# ndice.net
KiCad netlist of a schematic drawn in EAGLE
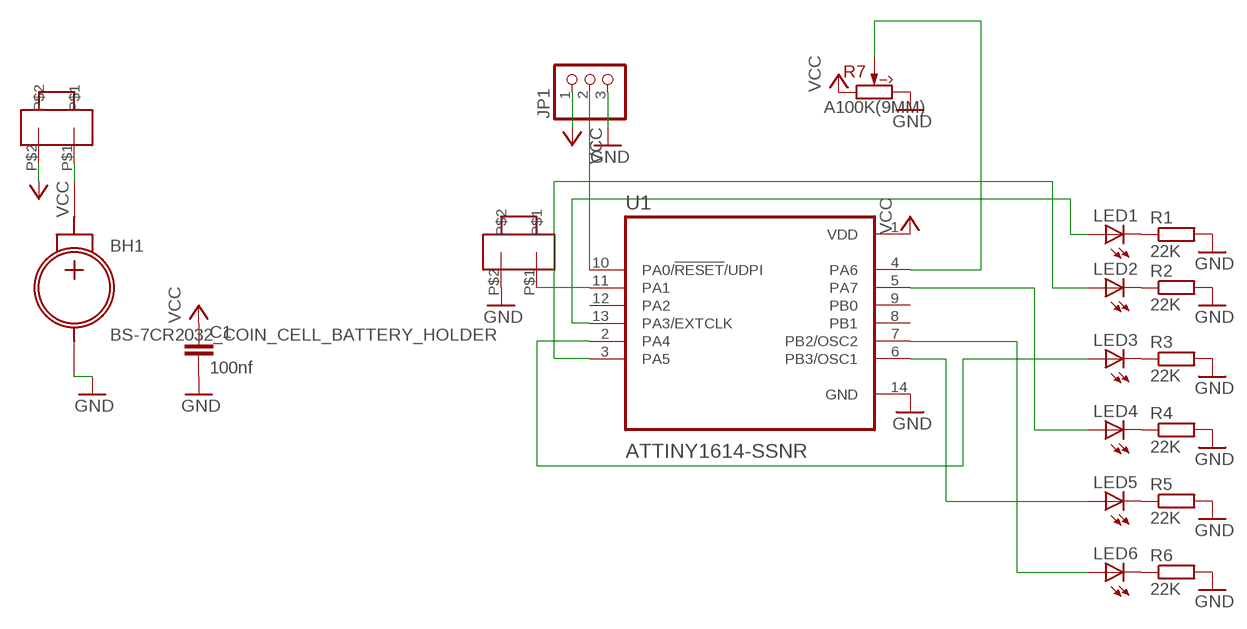
[diagram p0: schematic, sheet 1]

(export (version "E")
  (design (tool "Eeschema 10.0.6"))
  (components
    (comp (ref "BH1")
      (value "BS-7CR2032_COIN_CELL_BATTERY_HOLDER")
      (footprint "eagle-import:BS-7")
      (fields (field (name "MF") "MPD") (field (name "MP") "BS-7"))
      (libsource (lib "eagle-import") (part "BS-7CR2032_COIN_CELL_BATTERY_HOLDER"))
    )
    (comp (ref "C1")
      (value "100nf")
      (footprint "eagle-import:C0805")
      (libsource (lib "eagle-import") (part "C-EUC0805"))
    )
    (comp (ref "JP1")
      (value "PINHD-1X3CB")
      (footprint "eagle-import:1X03-CLEANBIG")
      (libsource (lib "eagle-import") (part "PINHD-1X3CB"))
    )
    (comp (ref "LED1")
      (value "LEDSML0805")
      (footprint "eagle-import:SML0805")
      (libsource (lib "eagle-import") (part "LEDSML0805"))
    )
    (comp (ref "LED2")
      (value "LEDSML0805")
      (footprint "eagle-import:SML0805")
      (libsource (lib "eagle-import") (part "LEDSML0805"))
    )
    (comp (ref "LED3")
      (value "LEDSML0805")
      (footprint "eagle-import:SML0805")
      (libsource (lib "eagle-import") (part "LEDSML0805"))
    )
    (comp (ref "LED4")
      (value "LEDSML0805")
      (footprint "eagle-import:SML0805")
      (libsource (lib "eagle-import") (part "LEDSML0805"))
    )
    (comp (ref "LED5")
      (value "LEDSML0805")
      (footprint "eagle-import:SML0805")
      (libsource (lib "eagle-import") (part "LEDSML0805"))
    )
    (comp (ref "LED6")
      (value "LEDSML0805")
      (footprint "eagle-import:SML0805")
      (libsource (lib "eagle-import") (part "LEDSML0805"))
    )
    (comp (ref "R1")
      (value "22K")
      (footprint "eagle-import:R0805")
      (libsource (lib "eagle-import") (part "R-EU_R0805"))
    )
    (comp (ref "R2")
      (value "22K")
      (footprint "eagle-import:R0805")
      (libsource (lib "eagle-import") (part "R-EU_R0805"))
    )
    (comp (ref "R3")
      (value "22K")
      (footprint "eagle-import:R0805")
      (libsource (lib "eagle-import") (part "R-EU_R0805"))
    )
    (comp (ref "R4")
      (value "22K")
      (footprint "eagle-import:R0805")
      (libsource (lib "eagle-import") (part "R-EU_R0805"))
    )
    (comp (ref "R5")
      (value "22K")
      (footprint "eagle-import:R0805")
      (libsource (lib "eagle-import") (part "R-EU_R0805"))
    )
    (comp (ref "R6")
      (value "22K")
      (footprint "eagle-import:R0805")
      (libsource (lib "eagle-import") (part "R-EU_R0805"))
    )
    (comp (ref "R7")
      (value "A100K(9MM)")
      (footprint "eagle-import:RV09-SINGLE")
      (libsource (lib "eagle-import") (part "?A100K(9MM)"))
    )
    (comp (ref "U$1")
      (value "SIDEBUTTON")
      (footprint "eagle-import:SMD")
      (libsource (lib "eagle-import") (part "SIDEBUTTON"))
    )
    (comp (ref "U$2")
      (value "SIDEBUTTON")
      (footprint "eagle-import:SMD")
      (libsource (lib "eagle-import") (part "SIDEBUTTON"))
    )
    (comp (ref "U1")
      (value "ATTINY1614-SSNR")
      (footprint "eagle-import:SOIC127P600X175-14N")
      (fields (field (name "MF") "Microchip"))
      (libsource (lib "eagle-import") (part "ATTINY1614-SSNR"))
    )
  )
  (nets
    (net (code "1") (name "GND") (class "Default")
      (node (ref "BH1") (pin "NEG") (pinfunction "NEG_NEG") (pintype "power_in"))
      (node (ref "C1") (pin "2") (pinfunction "2_2") (pintype "passive"))
      (node (ref "JP1") (pin "3") (pinfunction "3_3") (pintype "passive"))
      (node (ref "R1") (pin "2") (pinfunction "2_2") (pintype "passive"))
      (node (ref "R2") (pin "2") (pinfunction "2_2") (pintype "passive"))
      (node (ref "R3") (pin "2") (pinfunction "2_2") (pintype "passive"))
      (node (ref "R4") (pin "2") (pinfunction "2_2") (pintype "passive"))
      (node (ref "R5") (pin "2") (pinfunction "2_2") (pintype "passive"))
      (node (ref "R6") (pin "2") (pinfunction "2_2") (pintype "passive"))
      (node (ref "R7") (pin "3") (pinfunction "CW_3") (pintype "passive"))
      (node (ref "U$2") (pin "P$2") (pinfunction "P$2_P$2") (pintype "bidirectional"))
      (node (ref "U1") (pin "14") (pinfunction "GND_14") (pintype "power_in"))
    )
    (net (code "2") (name "Net-(BH1-PadPOS)") (class "Default")
      (node (ref "BH1") (pin "POS") (pinfunction "POS_POS") (pintype "power_in"))
      (node (ref "U$1") (pin "P$1") (pinfunction "P$1_P$1") (pintype "bidirectional"))
    )
    (net (code "3") (name "Net-(LED1-PadC)") (class "Default")
      (node (ref "LED1") (pin "C") (pinfunction "C_C") (pintype "passive"))
      (node (ref "R1") (pin "1") (pinfunction "1_1") (pintype "passive"))
    )
    (net (code "4") (name "Net-(LED2-PadC)") (class "Default")
      (node (ref "LED2") (pin "C") (pinfunction "C_C") (pintype "passive"))
      (node (ref "R2") (pin "1") (pinfunction "1_1") (pintype "passive"))
    )
    (net (code "5") (name "Net-(LED3-PadC)") (class "Default")
      (node (ref "LED3") (pin "C") (pinfunction "C_C") (pintype "passive"))
      (node (ref "R3") (pin "1") (pinfunction "1_1") (pintype "passive"))
    )
    (net (code "6") (name "Net-(LED4-PadC)") (class "Default")
      (node (ref "LED4") (pin "C") (pinfunction "C_C") (pintype "passive"))
      (node (ref "R4") (pin "1") (pinfunction "1_1") (pintype "passive"))
    )
    (net (code "7") (name "Net-(LED5-PadC)") (class "Default")
      (node (ref "LED5") (pin "C") (pinfunction "C_C") (pintype "passive"))
      (node (ref "R5") (pin "1") (pinfunction "1_1") (pintype "passive"))
    )
    (net (code "8") (name "Net-(LED6-PadC)") (class "Default")
      (node (ref "LED6") (pin "C") (pinfunction "C_C") (pintype "passive"))
      (node (ref "R6") (pin "1") (pinfunction "1_1") (pintype "passive"))
    )
    (net (code "9") (name "Net-(R7-W)") (class "Default")
      (node (ref "R7") (pin "2") (pinfunction "W_2") (pintype "passive"))
      (node (ref "U1") (pin "4") (pinfunction "PA6_4") (pintype "bidirectional"))
    )
    (net (code "10") (name "Net-(U1-PA0{slash}~{RESET}{slash}UDPI)") (class "Default")
      (node (ref "JP1") (pin "2") (pinfunction "2_2") (pintype "passive"))
      (node (ref "U1") (pin "10") (pinfunction "PA0/~{RESET}/UDPI_10") (pintype "bidirectional"))
    )
    (net (code "11") (name "Net-(U1-PA1)") (class "Default")
      (node (ref "U$2") (pin "P$1") (pinfunction "P$1_P$1") (pintype "bidirectional"))
      (node (ref "U1") (pin "11") (pinfunction "PA1_11") (pintype "bidirectional"))
    )
    (net (code "12") (name "Net-(U1-PA3{slash}EXTCLK)") (class "Default")
      (node (ref "LED1") (pin "A") (pinfunction "A_A") (pintype "passive"))
      (node (ref "U1") (pin "13") (pinfunction "PA3/EXTCLK_13") (pintype "bidirectional"))
    )
    (net (code "13") (name "Net-(U1-PA4)") (class "Default")
      (node (ref "LED3") (pin "A") (pinfunction "A_A") (pintype "passive"))
      (node (ref "U1") (pin "2") (pinfunction "PA4_2") (pintype "bidirectional"))
    )
    (net (code "14") (name "Net-(U1-PA5)") (class "Default")
      (node (ref "LED2") (pin "A") (pinfunction "A_A") (pintype "passive"))
      (node (ref "U1") (pin "3") (pinfunction "PA5_3") (pintype "bidirectional"))
    )
    (net (code "15") (name "Net-(U1-PA7)") (class "Default")
      (node (ref "LED4") (pin "A") (pinfunction "A_A") (pintype "passive"))
      (node (ref "U1") (pin "5") (pinfunction "PA7_5") (pintype "bidirectional"))
    )
    (net (code "16") (name "Net-(U1-PB2{slash}OSC2)") (class "Default")
      (node (ref "LED6") (pin "A") (pinfunction "A_A") (pintype "passive"))
      (node (ref "U1") (pin "7") (pinfunction "PB2/OSC2_7") (pintype "bidirectional"))
    )
    (net (code "17") (name "Net-(U1-PB3{slash}OSC1)") (class "Default")
      (node (ref "LED5") (pin "A") (pinfunction "A_A") (pintype "passive"))
      (node (ref "U1") (pin "6") (pinfunction "PB3/OSC1_6") (pintype "bidirectional"))
    )
    (net (code "18") (name "VCC") (class "Default")
      (node (ref "C1") (pin "1") (pinfunction "1_1") (pintype "passive"))
      (node (ref "JP1") (pin "1") (pinfunction "1_1") (pintype "passive"))
      (node (ref "R7") (pin "1") (pinfunction "CCW_1") (pintype "passive"))
      (node (ref "U$1") (pin "P$2") (pinfunction "P$2_P$2") (pintype "bidirectional"))
      (node (ref "U1") (pin "1") (pinfunction "VDD_1") (pintype "power_in"))
    )
    (net (code "19") (name "unconnected-(U1-PA2-Pad12)") (class "Default")
      (node (ref "U1") (pin "12") (pinfunction "PA2_12") (pintype "bidirectional"))
    )
    (net (code "20") (name "unconnected-(U1-PB0-Pad9)") (class "Default")
      (node (ref "U1") (pin "9") (pinfunction "PB0_9") (pintype "bidirectional"))
    )
    (net (code "21") (name "unconnected-(U1-PB1-Pad8)") (class "Default")
      (node (ref "U1") (pin "8") (pinfunction "PB1_8") (pintype "bidirectional"))
    )
  )
)
